# PATHOS_PowerSwitch.net
KiCad netlist of a schematic drawn in Altium Designer
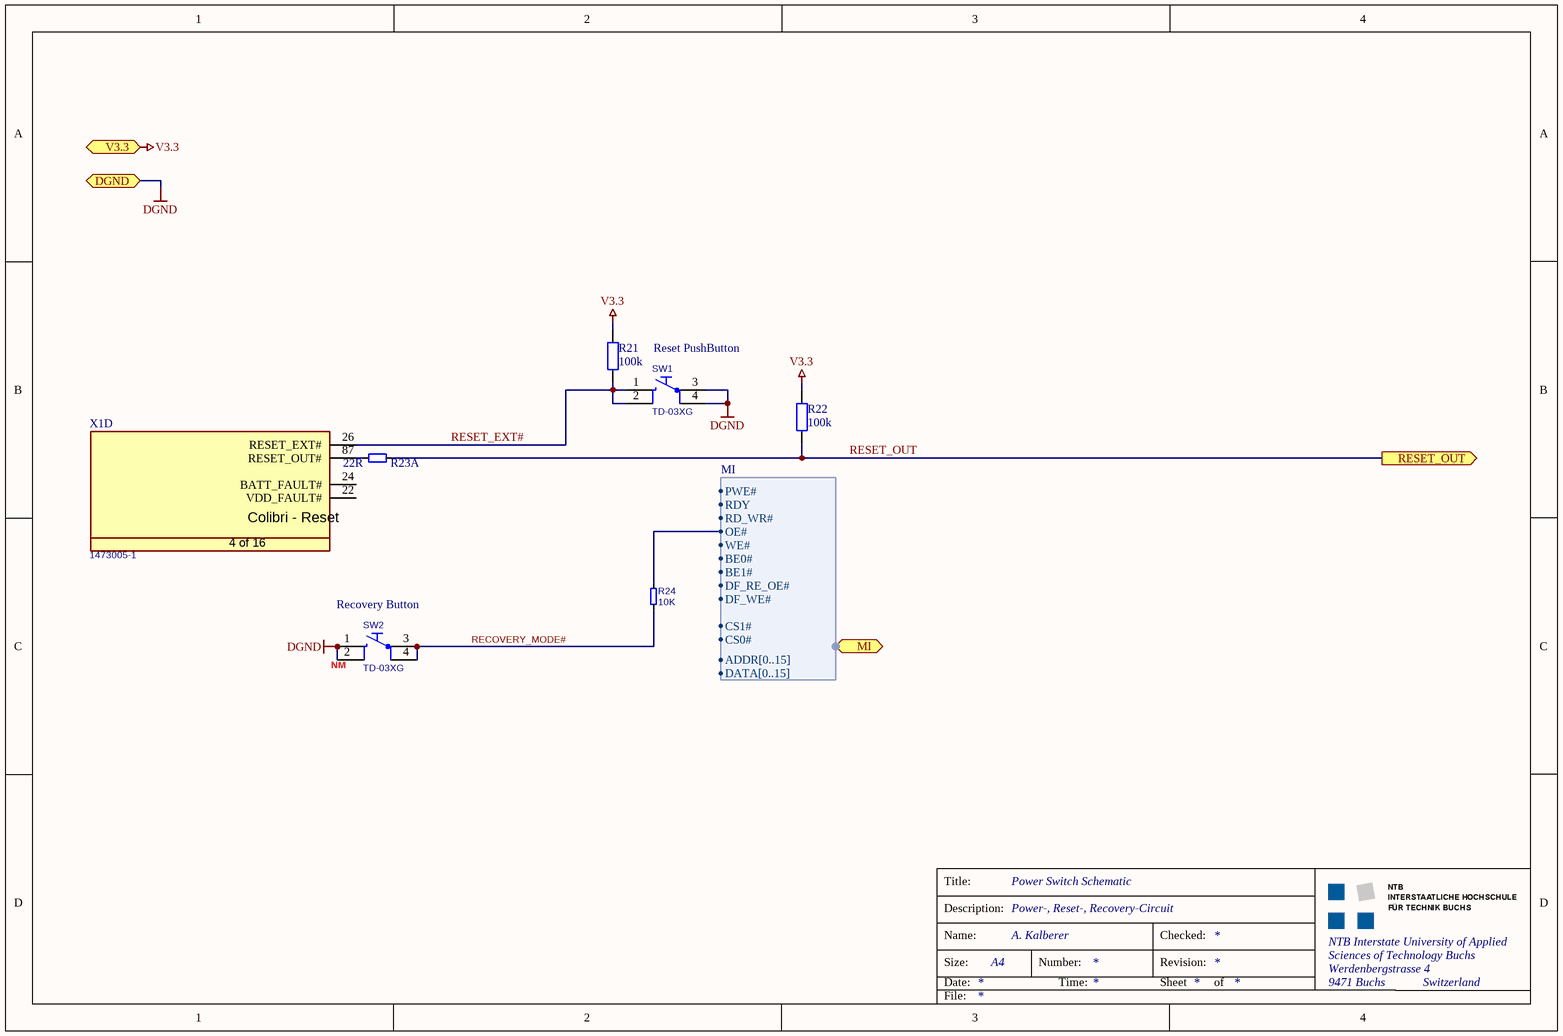
[diagram p0: PATHOS_PowerSwitch.SchDoc]

(export (version "E")
  (design (tool "Eeschema 10.0.6"))
  (components
    (comp (ref "R21")
      (value "100k")
      (footprint "0603_3D")
      (description "Resistor")
      (fields (field (name "#PUBLISHER") "Dr. A. Heinzelmann"))
      (libsource (lib "ELE-LIB") (part "R"))
    )
    (comp (ref "R22")
      (value "100k")
      (footprint "0603_3D")
      (description "Resistor")
      (fields (field (name "#PUBLISHER") "Dr. A. Heinzelmann"))
      (libsource (lib "ELE-LIB") (part "R"))
    )
    (comp (ref "R23")
      (value "22R")
      (footprint "R_Array_CAT16-J4")
      (fields (field (name "Comment") "R Array"))
      (libsource (lib "EFSSensorboard_1") (part "R_Array"))
    )
    (comp (ref "R24")
      (value "10K")
      (footprint "0603_3D")
      (description "Resistor 10 Kohm 63mW 5% 0603")
      (fields (field (name "TOLERANCE") "5%"))
      (libsource (lib "Evaluation Board") (part "R-10KR-63mW-5%-0603"))
    )
    (comp (ref "SW1")
      (value "TD-03XG")
      (footprint "T_WMF_TD-03XG")
      (description "Switch")
      (libsource (lib "Evaluation Board") (part "SW-WMF-TD-03XG"))
    )
    (comp (ref "SW2")
      (value "TD-03XG")
      (footprint "T_WMF_TD-03XG")
      (description "Switch")
      (libsource (lib "Evaluation Board") (part "SW-WMF-TD-03XG"))
    )
    (comp (ref "X1")
      (value "CON-Tyco-1473005-1-200-0.6mm")
      (footprint "T_Tyco_1473005-1")
      (description "SODIMM Connector")
      (fields (field (name "MANUFACTURER PART NO.") "1473005-1"))
      (libsource (lib "EFS_Sensorboard") (part "CON-Tyco-1473005-1-200-0.6mm"))
    )
  )
  (nets
    (net (code "2") (name "/OE#") (class "Default")
      (node (ref "R24") (pin "2") (pinfunction "2_2") (pintype "passive"))
    )
    (net (code "3") (name "/RECOVERY_MODE#") (class "Default")
      (node (ref "R24") (pin "1") (pinfunction "1_1") (pintype "passive"))
      (node (ref "SW2") (pin "3") (pinfunction "3_3") (pintype "passive"))
      (node (ref "SW2") (pin "4") (pinfunction "4_4") (pintype "passive"))
    )
    (net (code "4") (name "/RESET_EXT#") (class "Default")
      (node (ref "R21") (pin "1") (pinfunction "1_1") (pintype "passive"))
      (node (ref "SW1") (pin "1") (pinfunction "1_1") (pintype "passive"))
      (node (ref "SW1") (pin "2") (pinfunction "2_2") (pintype "passive"))
      (node (ref "X1") (pin "26") (pinfunction "RESET_EXT#_26") (pintype "passive"))
    )
    (net (code "5") (name "/RESET_OUT") (class "Default")
      (node (ref "R22") (pin "1") (pinfunction "1_1") (pintype "passive"))
      (node (ref "R23") (pin "1A") (pinfunction "1_1A") (pintype "passive"))
    )
    (net (code "7") (name "DGND") (class "Default")
      (node (ref "SW1") (pin "3") (pinfunction "3_3") (pintype "passive"))
      (node (ref "SW1") (pin "4") (pinfunction "4_4") (pintype "passive"))
      (node (ref "SW2") (pin "1") (pinfunction "1_1") (pintype "passive"))
      (node (ref "SW2") (pin "2") (pinfunction "2_2") (pintype "passive"))
    )
    (net (code "8") (name "Net-(R23A-2)") (class "Default")
      (node (ref "R23") (pin "2A") (pinfunction "2_2A") (pintype "passive"))
      (node (ref "X1") (pin "87") (pinfunction "RESET_OUT#_87") (pintype "passive"))
    )
    (net (code "9") (name "V3.3") (class "Default")
      (node (ref "R21") (pin "2") (pinfunction "2_2") (pintype "passive"))
      (node (ref "R22") (pin "2") (pinfunction "2_2") (pintype "passive"))
    )
    (net (code "10") (name "unconnected-(X1D-BATT_FAULT#-Pad24)") (class "Default")
      (node (ref "X1") (pin "24") (pinfunction "BATT_FAULT#_24") (pintype "passive"))
    )
    (net (code "11") (name "unconnected-(X1D-VDD_FAULT#-Pad22)") (class "Default")
      (node (ref "X1") (pin "22") (pinfunction "VDD_FAULT#_22") (pintype "passive"))
    )
  )
)
